# LM-008.net
KiCad netlist of a schematic drawn in Altium Designer
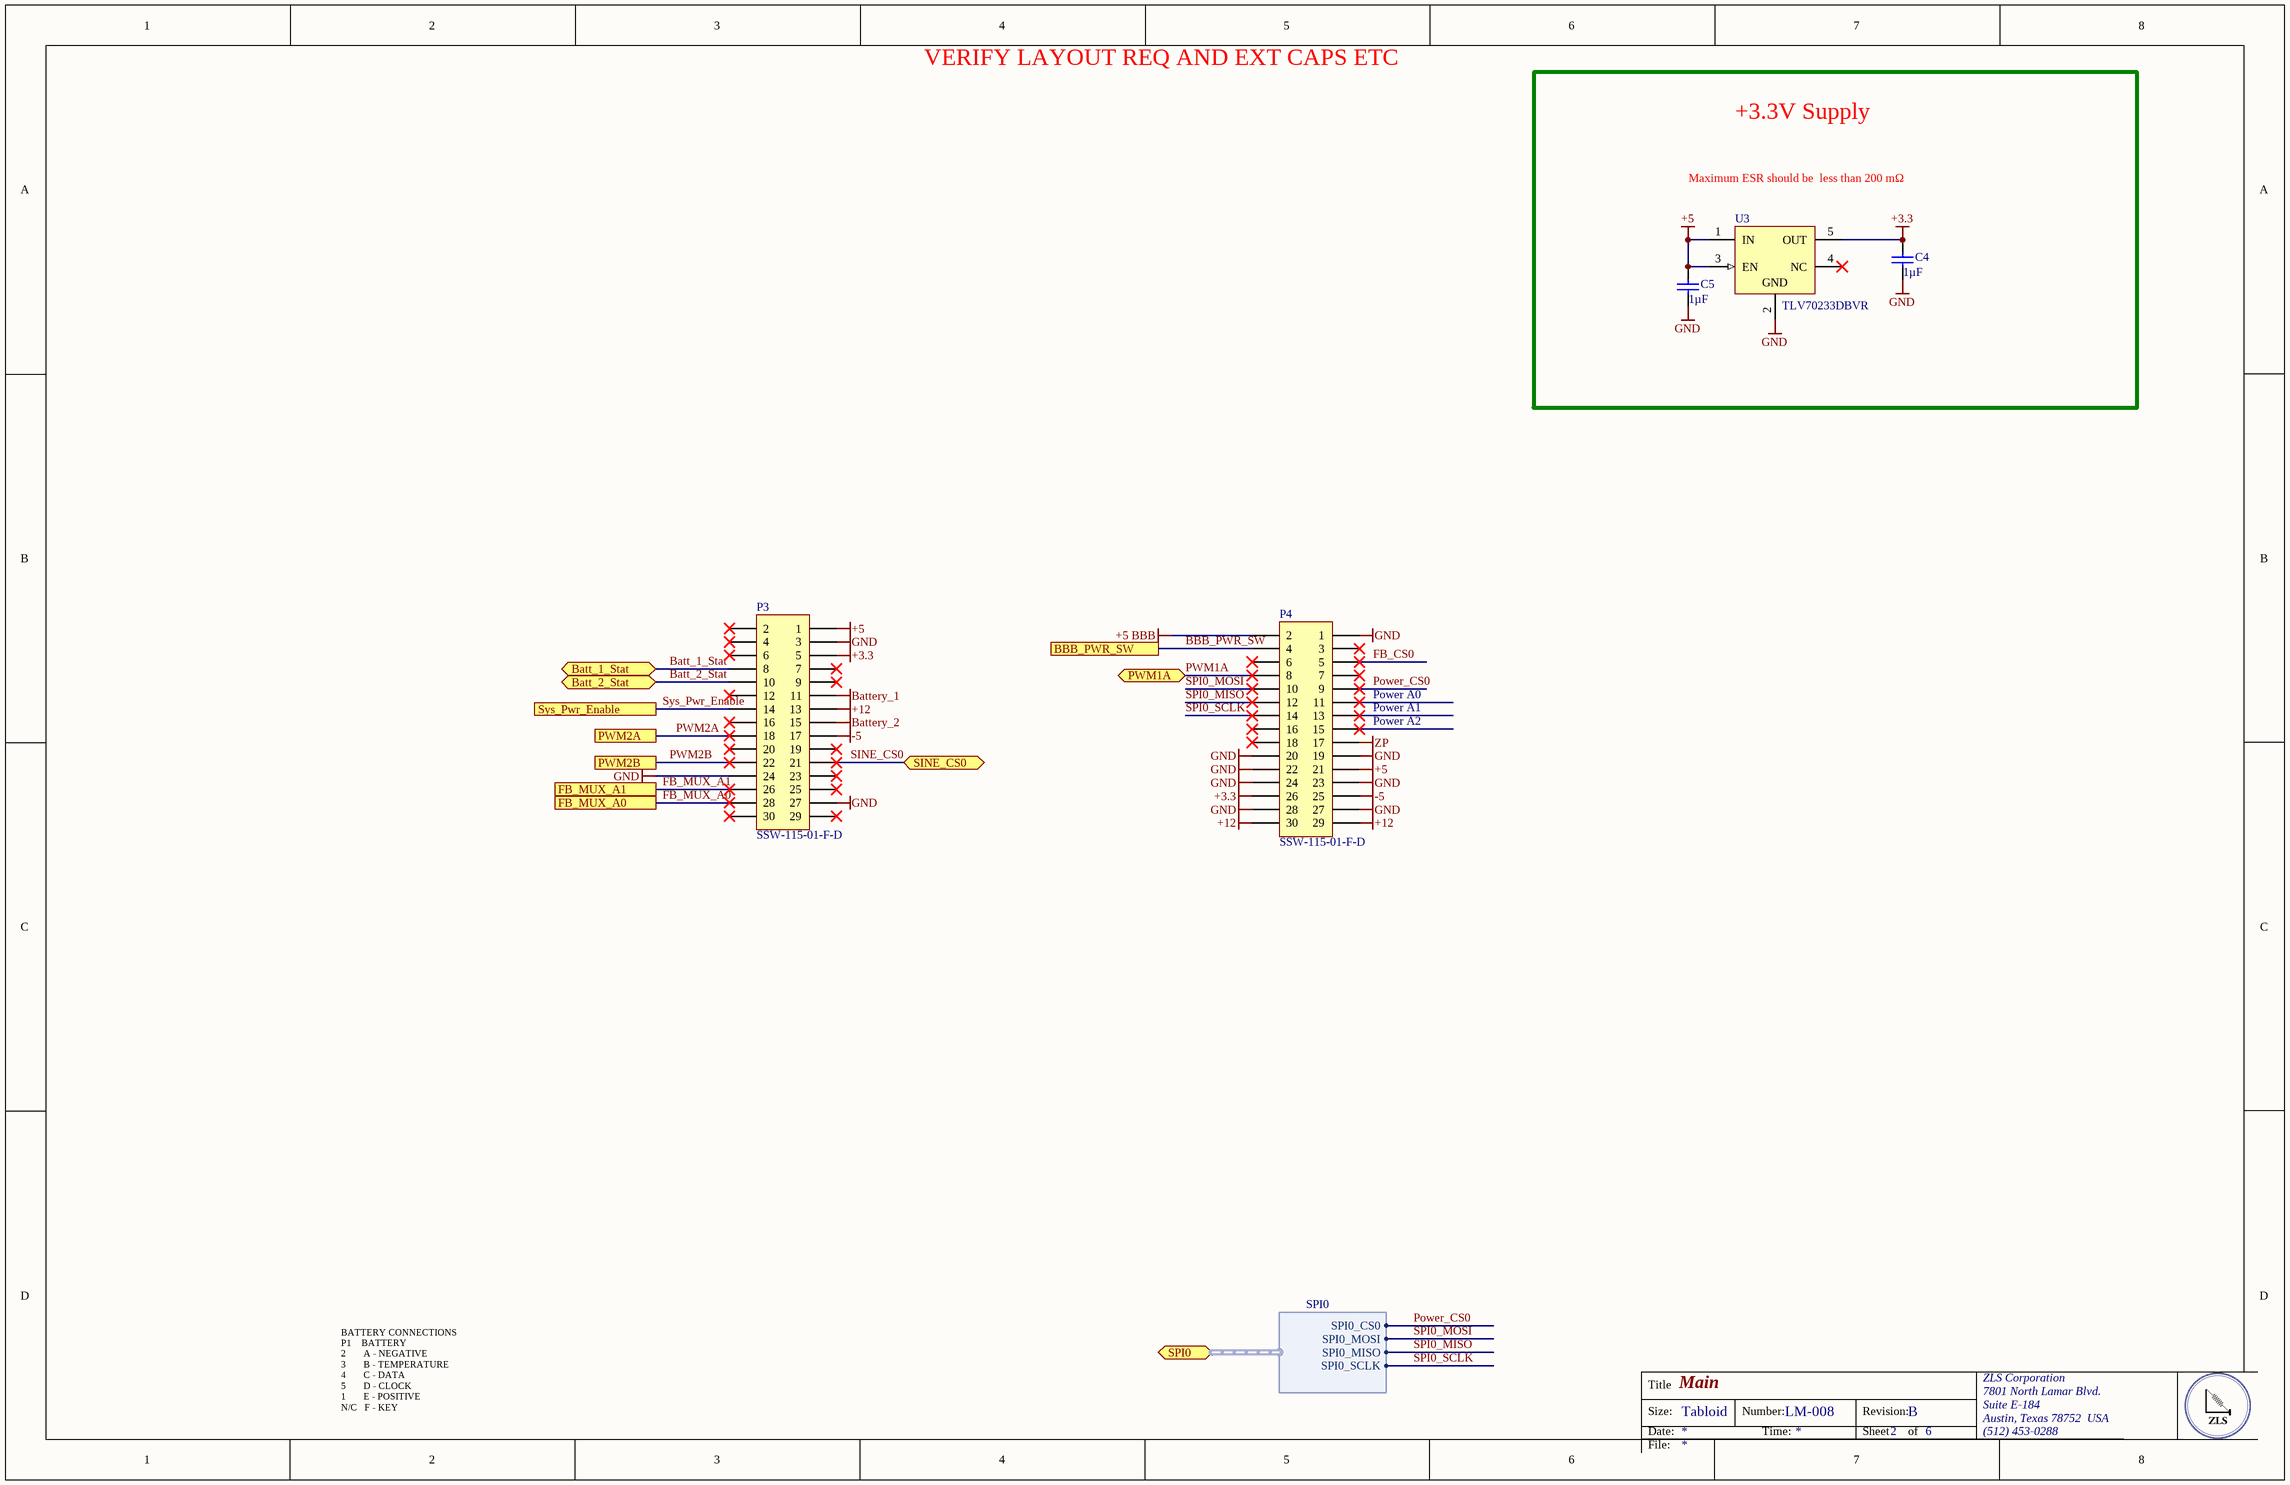
[diagram p0: LM-008.SchDoc]

(export (version "E")
  (design (tool "Eeschema 10.0.6"))
  (components
    (comp (ref "C4")
      (value "CAP CER 1UF 50V X7R 1210")
      (footprint "CAPC1206(3216)130_N")
      (fields
        (field (name "MANUFACTURER") "Murata Electronics North America")
        (field (name "MANUFACTURER PART NUMBER") "GRM32RR71H105KA01L")
        (field (name "CAPACITANCE") "1µF")
        (field (name "TOLERANCE") "±10%")
      )
      (libsource (lib "Altium Content Vault") (part "CMP-1037-04913-1"))
    )
    (comp (ref "C5")
      (value "CAP CER 1UF 50V X7R 1210")
      (footprint "CAPC1206(3216)130_N")
      (fields
        (field (name "MANUFACTURER") "Murata Electronics North America")
        (field (name "MANUFACTURER PART NUMBER") "GRM32RR71H105KA01L")
        (field (name "CAPACITANCE") "1µF")
        (field (name "TOLERANCE") "±10%")
      )
      (libsource (lib "Altium Content Vault") (part "CMP-1037-04913-1"))
    )
    (comp (ref "P3")
      (value "SSW-115-01-F-D")
      (footprint "SSW-115-23-G-D")
      (description "Header, 15-Pin, Dual row")
      (fields (field (name "MANUFACTURER") "Samtec Inc."))
      (libsource (lib "Miscellaneous Connectors") (part "Header 15X2"))
    )
    (comp (ref "P4")
      (value "SSW-115-01-F-D")
      (footprint "SSW-115-23-G-D")
      (description "Header, 15-Pin, Dual row")
      (fields (field (name "MANUFACTURER") "Samtec Inc."))
      (libsource (lib "Miscellaneous Connectors") (part "Header 15X2"))
    )
    (comp (ref "U3")
      (value "TLV70233DBVR")
      (footprint "DBV0005A_N")
      (fields (field (name "MANUFACTURER") "Texas Instruments") (field (name "BASE PART NUMBER") "TLV70233"))
      (libsource (lib "Altium Content Vault") (part "CMP-0394-00528-2"))
    )
  )
  (nets
    (net (code "2") (name "+3.3") (class "Default")
      (node (ref "C4") (pin "2") (pinfunction "2_2") (pintype "passive"))
      (node (ref "P3") (pin "5") (pinfunction "5_5") (pintype "passive"))
      (node (ref "P4") (pin "26") (pinfunction "26_26") (pintype "passive"))
      (node (ref "U3") (pin "5") (pinfunction "OUT_5") (pintype "power_in"))
    )
    (net (code "3") (name "+5") (class "Default")
      (node (ref "C5") (pin "2") (pinfunction "2_2") (pintype "passive"))
      (node (ref "P3") (pin "1") (pinfunction "1_1") (pintype "passive"))
      (node (ref "P4") (pin "21") (pinfunction "21_21") (pintype "passive"))
      (node (ref "U3") (pin "1") (pinfunction "IN_1") (pintype "power_in"))
      (node (ref "U3") (pin "3") (pinfunction "EN_3") (pintype "input"))
    )
    (net (code "4") (name "+5 BBB") (class "Default")
      (node (ref "P4") (pin "2") (pinfunction "2_2") (pintype "passive"))
    )
    (net (code "5") (name "+12") (class "Default")
      (node (ref "P3") (pin "13") (pinfunction "13_13") (pintype "passive"))
      (node (ref "P4") (pin "29") (pinfunction "29_29") (pintype "passive"))
      (node (ref "P4") (pin "30") (pinfunction "30_30") (pintype "passive"))
    )
    (net (code "6") (name "-5") (class "Default")
      (node (ref "P3") (pin "17") (pinfunction "17_17") (pintype "passive"))
      (node (ref "P4") (pin "25") (pinfunction "25_25") (pintype "passive"))
    )
    (net (code "7") (name "/BBB_PWR_SW") (class "Default")
      (node (ref "P4") (pin "4") (pinfunction "4_4") (pintype "passive"))
    )
    (net (code "8") (name "/Batt_1_Stat") (class "Default")
      (node (ref "P3") (pin "8") (pinfunction "8_8") (pintype "passive"))
    )
    (net (code "9") (name "/Batt_2_Stat") (class "Default")
      (node (ref "P3") (pin "10") (pinfunction "10_10") (pintype "passive"))
    )
    (net (code "10") (name "/FB_CS0") (class "Default")
      (node (ref "P4") (pin "5") (pinfunction "5_5") (pintype "passive+no_connect"))
    )
    (net (code "11") (name "/FB_MUX_A0") (class "Default")
      (node (ref "P3") (pin "28") (pinfunction "28_28") (pintype "passive+no_connect"))
    )
    (net (code "12") (name "/FB_MUX_A1") (class "Default")
      (node (ref "P3") (pin "26") (pinfunction "26_26") (pintype "passive+no_connect"))
    )
    (net (code "13") (name "/PWM1A") (class "Default")
      (node (ref "P4") (pin "8") (pinfunction "8_8") (pintype "passive+no_connect"))
    )
    (net (code "14") (name "/PWM2A") (class "Default")
      (node (ref "P3") (pin "18") (pinfunction "18_18") (pintype "passive+no_connect"))
    )
    (net (code "15") (name "/PWM2B") (class "Default")
      (node (ref "P3") (pin "22") (pinfunction "22_22") (pintype "passive+no_connect"))
    )
    (net (code "16") (name "/Power_CS0") (class "Default")
      (node (ref "P4") (pin "9") (pinfunction "9_9") (pintype "passive+no_connect"))
    )
    (net (code "17") (name "/SINE_CS0") (class "Default")
      (node (ref "P3") (pin "21") (pinfunction "21_21") (pintype "passive+no_connect"))
    )
    (net (code "18") (name "/SPI0_MISO") (class "Default")
      (node (ref "P4") (pin "12") (pinfunction "12_12") (pintype "passive"))
    )
    (net (code "19") (name "/SPI0_MOSI") (class "Default")
      (node (ref "P4") (pin "10") (pinfunction "10_10") (pintype "passive"))
    )
    (net (code "20") (name "/SPI0_SCLK") (class "Default")
      (node (ref "P4") (pin "14") (pinfunction "14_14") (pintype "passive"))
    )
    (net (code "21") (name "/Sys_Pwr_Enable") (class "Default")
      (node (ref "P3") (pin "14") (pinfunction "14_14") (pintype "passive"))
    )
    (net (code "23") (name "Battery_1") (class "Default")
      (node (ref "P3") (pin "11") (pinfunction "11_11") (pintype "passive"))
    )
    (net (code "24") (name "Battery_2") (class "Default")
      (node (ref "P3") (pin "15") (pinfunction "15_15") (pintype "passive"))
    )
    (net (code "25") (name "GND") (class "Default")
      (node (ref "C4") (pin "1") (pinfunction "1_1") (pintype "passive"))
      (node (ref "C5") (pin "1") (pinfunction "1_1") (pintype "passive"))
      (node (ref "P3") (pin "24") (pinfunction "24_24") (pintype "passive"))
      (node (ref "P3") (pin "27") (pinfunction "27_27") (pintype "passive"))
      (node (ref "P3") (pin "3") (pinfunction "3_3") (pintype "passive"))
      (node (ref "P4") (pin "1") (pinfunction "1_1") (pintype "passive"))
      (node (ref "P4") (pin "19") (pinfunction "19_19") (pintype "passive"))
      (node (ref "P4") (pin "20") (pinfunction "20_20") (pintype "passive"))
      (node (ref "P4") (pin "22") (pinfunction "22_22") (pintype "passive"))
      (node (ref "P4") (pin "23") (pinfunction "23_23") (pintype "passive"))
      (node (ref "P4") (pin "24") (pinfunction "24_24") (pintype "passive"))
      (node (ref "P4") (pin "27") (pinfunction "27_27") (pintype "passive"))
      (node (ref "P4") (pin "28") (pinfunction "28_28") (pintype "passive"))
      (node (ref "U3") (pin "2") (pinfunction "GND_2") (pintype "power_in"))
    )
    (net (code "26") (name "ZP") (class "Default")
      (node (ref "P4") (pin "17") (pinfunction "17_17") (pintype "passive"))
    )
    (net (code "27") (name "unconnected-(P3-Pad2)") (class "Default")
      (node (ref "P3") (pin "2") (pinfunction "2_2") (pintype "passive+no_connect"))
    )
    (net (code "28") (name "unconnected-(P3-Pad4)") (class "Default")
      (node (ref "P3") (pin "4") (pinfunction "4_4") (pintype "passive+no_connect"))
    )
    (net (code "29") (name "unconnected-(P3-Pad6)") (class "Default")
      (node (ref "P3") (pin "6") (pinfunction "6_6") (pintype "passive+no_connect"))
    )
    (net (code "30") (name "unconnected-(P3-Pad7)") (class "Default")
      (node (ref "P3") (pin "7") (pinfunction "7_7") (pintype "passive+no_connect"))
    )
    (net (code "31") (name "unconnected-(P3-Pad9)") (class "Default")
      (node (ref "P3") (pin "9") (pinfunction "9_9") (pintype "passive+no_connect"))
    )
    (net (code "32") (name "unconnected-(P3-Pad12)") (class "Default")
      (node (ref "P3") (pin "12") (pinfunction "12_12") (pintype "passive+no_connect"))
    )
    (net (code "33") (name "unconnected-(P3-Pad16)") (class "Default")
      (node (ref "P3") (pin "16") (pinfunction "16_16") (pintype "passive+no_connect"))
    )
    (net (code "34") (name "unconnected-(P3-Pad19)") (class "Default")
      (node (ref "P3") (pin "19") (pinfunction "19_19") (pintype "passive+no_connect"))
    )
    (net (code "35") (name "unconnected-(P3-Pad20)") (class "Default")
      (node (ref "P3") (pin "20") (pinfunction "20_20") (pintype "passive+no_connect"))
    )
    (net (code "36") (name "unconnected-(P3-Pad23)") (class "Default")
      (node (ref "P3") (pin "23") (pinfunction "23_23") (pintype "passive+no_connect"))
    )
    (net (code "37") (name "unconnected-(P3-Pad25)") (class "Default")
      (node (ref "P3") (pin "25") (pinfunction "25_25") (pintype "passive+no_connect"))
    )
    (net (code "38") (name "unconnected-(P3-Pad29)") (class "Default")
      (node (ref "P3") (pin "29") (pinfunction "29_29") (pintype "passive+no_connect"))
    )
    (net (code "39") (name "unconnected-(P3-Pad30)") (class "Default")
      (node (ref "P3") (pin "30") (pinfunction "30_30") (pintype "passive+no_connect"))
    )
    (net (code "40") (name "unconnected-(P4-Pad3)") (class "Default")
      (node (ref "P4") (pin "3") (pinfunction "3_3") (pintype "passive+no_connect"))
    )
    (net (code "41") (name "unconnected-(P4-Pad6)") (class "Default")
      (node (ref "P4") (pin "6") (pinfunction "6_6") (pintype "passive+no_connect"))
    )
    (net (code "42") (name "unconnected-(P4-Pad7)") (class "Default")
      (node (ref "P4") (pin "7") (pinfunction "7_7") (pintype "passive+no_connect"))
    )
    (net (code "43") (name "unconnected-(P4-Pad11)") (class "Default")
      (node (ref "P4") (pin "11") (pinfunction "11_11") (pintype "passive+no_connect"))
    )
    (net (code "44") (name "unconnected-(P4-Pad13)") (class "Default")
      (node (ref "P4") (pin "13") (pinfunction "13_13") (pintype "passive+no_connect"))
    )
    (net (code "45") (name "unconnected-(P4-Pad15)") (class "Default")
      (node (ref "P4") (pin "15") (pinfunction "15_15") (pintype "passive+no_connect"))
    )
    (net (code "46") (name "unconnected-(P4-Pad16)") (class "Default")
      (node (ref "P4") (pin "16") (pinfunction "16_16") (pintype "passive+no_connect"))
    )
    (net (code "47") (name "unconnected-(P4-Pad18)") (class "Default")
      (node (ref "P4") (pin "18") (pinfunction "18_18") (pintype "passive+no_connect"))
    )
    (net (code "48") (name "unconnected-(U3-NC-Pad4)") (class "Default")
      (node (ref "U3") (pin "4") (pinfunction "NC_4") (pintype "passive+no_connect"))
    )
  )
)
